# circuito.net
KiCad netlist of a schematic drawn in EAGLE
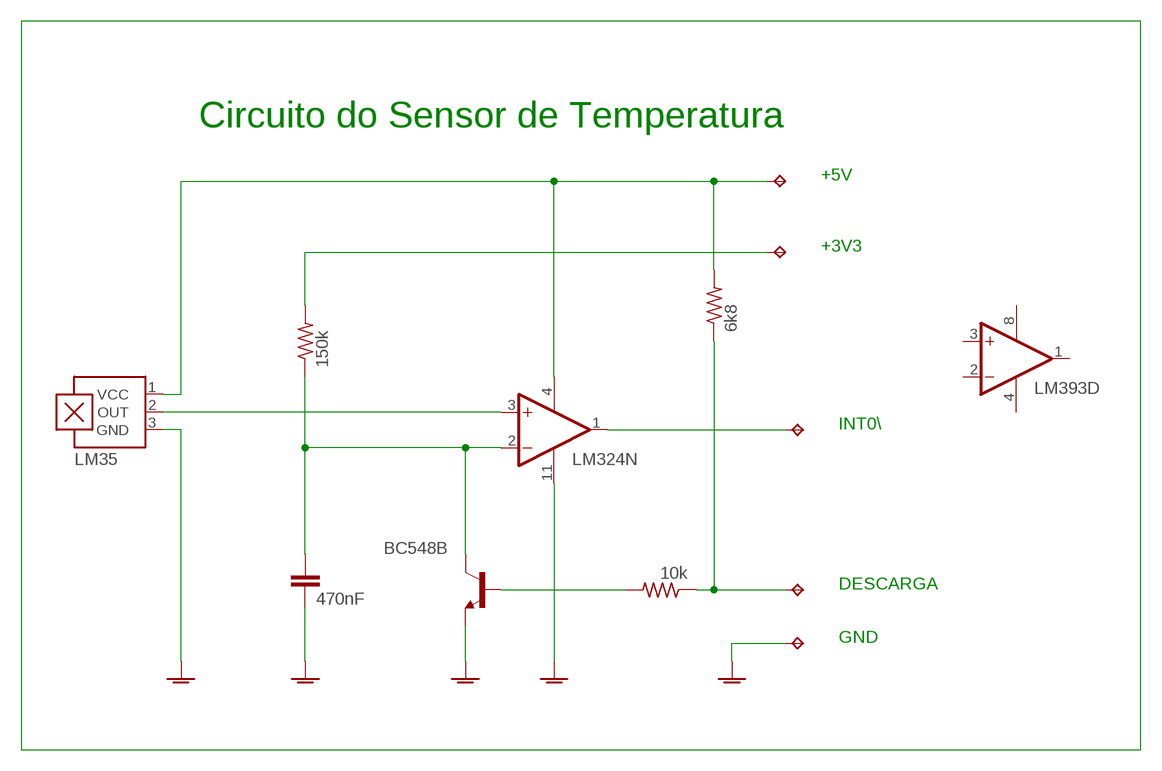
[diagram p0: schematic, sheet 1]

(export (version "E")
  (design (tool "Eeschema 10.0.6"))
  (components
    (comp (ref "C1")
      (value "470nF")
      (footprint "eagle-import:C2.5-3")
      (libsource (lib "eagle-import") (part "C2,5-3"))
    )
    (comp (ref "IC1")
      (value "LM324N")
      (footprint "eagle-import:DIL14")
      (libsource (lib "eagle-import") (part "LM324N"))
    )
    (comp (ref "IC2")
      (value "LM393D")
      (footprint "eagle-import:SO08")
      (libsource (lib "eagle-import") (part "LM393D"))
    )
    (comp (ref "IC3")
      (value "LM35")
      (footprint "eagle-import:SOT23-W")
      (fields (field (name "MF") "ALLEGRO MICROSYSTEMS, INC.") (field (name "MPN") "A1301ELHLT-T"))
      (libsource (lib "eagle-import") (part "A13?LH01"))
    )
    (comp (ref "Q1")
      (value "BC548B")
      (footprint "eagle-import:TO92-EBC")
      (libsource (lib "eagle-import") (part "BC548B"))
    )
    (comp (ref "R1")
      (value "150k")
      (footprint "eagle-import:0207_10")
      (libsource (lib "eagle-import") (part "R-US_0207/10"))
    )
    (comp (ref "R2")
      (value "10k")
      (footprint "eagle-import:0207_10")
      (libsource (lib "eagle-import") (part "R-US_0207/10"))
    )
    (comp (ref "R3")
      (value "6k8")
      (footprint "eagle-import:0207_10")
      (libsource (lib "eagle-import") (part "R-US_0207/10"))
    )
    (comp (ref "TP1")
      (value "TPB1,27")
      (footprint "eagle-import:B1,27")
      (libsource (lib "eagle-import") (part "TPB1,27"))
    )
    (comp (ref "TP2")
      (value "TPB1,27")
      (footprint "eagle-import:B1,27")
      (libsource (lib "eagle-import") (part "TPB1,27"))
    )
    (comp (ref "TP3")
      (value "TPB1,27")
      (footprint "eagle-import:B1,27")
      (libsource (lib "eagle-import") (part "TPB1,27"))
    )
    (comp (ref "TP4")
      (value "TPB1,27")
      (footprint "eagle-import:B1,27")
      (libsource (lib "eagle-import") (part "TPB1,27"))
    )
    (comp (ref "TP5")
      (value "TPB1,27")
      (footprint "eagle-import:B1,27")
      (libsource (lib "eagle-import") (part "TPB1,27"))
    )
  )
  (nets
    (net (code "1") (name "/V+") (class "Default")
      (node (ref "IC2") (pin "8") (pinfunction "V+_8") (pintype "power_in"))
    )
    (net (code "2") (name "/V-") (class "Default")
      (node (ref "IC2") (pin "4") (pinfunction "V-_4") (pintype "power_in"))
    )
    (net (code "3") (name "GNDA") (class "Default")
      (node (ref "C1") (pin "2") (pinfunction "2_2") (pintype "passive"))
      (node (ref "IC1") (pin "11") (pinfunction "V-_11") (pintype "power_in"))
      (node (ref "IC3") (pin "3") (pinfunction "GND_3") (pintype "power_in"))
      (node (ref "Q1") (pin "E") (pinfunction "E_E") (pintype "passive"))
      (node (ref "TP2") (pin "TP") (pinfunction "TP_TP") (pintype "input"))
    )
    (net (code "4") (name "Net-(IC1A-+IN)") (class "Default")
      (node (ref "IC1") (pin "3") (pinfunction "+IN_3") (pintype "input"))
      (node (ref "IC3") (pin "2") (pinfunction "OUT_2") (pintype "output"))
    )
    (net (code "5") (name "Net-(IC1A--IN)") (class "Default")
      (node (ref "C1") (pin "1") (pinfunction "1_1") (pintype "passive"))
      (node (ref "IC1") (pin "2") (pinfunction "-IN_2") (pintype "input"))
      (node (ref "Q1") (pin "C") (pinfunction "C_C") (pintype "passive"))
      (node (ref "R1") (pin "1") (pinfunction "1_1") (pintype "passive"))
    )
    (net (code "6") (name "Net-(IC1A-OUT)") (class "Default")
      (node (ref "IC1") (pin "1") (pinfunction "OUT_1") (pintype "output"))
      (node (ref "TP4") (pin "TP") (pinfunction "TP_TP") (pintype "input"))
    )
    (net (code "7") (name "Net-(IC1E-V+)") (class "Default")
      (node (ref "IC1") (pin "4") (pinfunction "V+_4") (pintype "power_in"))
      (node (ref "IC3") (pin "1") (pinfunction "VCC_1") (pintype "power_in"))
      (node (ref "R3") (pin "2") (pinfunction "2_2") (pintype "passive"))
      (node (ref "TP1") (pin "TP") (pinfunction "TP_TP") (pintype "input"))
    )
    (net (code "8") (name "Net-(Q1-PadB)") (class "Default")
      (node (ref "Q1") (pin "B") (pinfunction "B_B") (pintype "passive"))
      (node (ref "R2") (pin "2") (pinfunction "2_2") (pintype "passive"))
    )
    (net (code "9") (name "Net-(R1-Pad2)") (class "Default")
      (node (ref "R1") (pin "2") (pinfunction "2_2") (pintype "passive"))
      (node (ref "TP5") (pin "TP") (pinfunction "TP_TP") (pintype "input"))
    )
    (net (code "10") (name "Net-(R2-Pad1)") (class "Default")
      (node (ref "R2") (pin "1") (pinfunction "1_1") (pintype "passive"))
      (node (ref "R3") (pin "1") (pinfunction "1_1") (pintype "passive"))
      (node (ref "TP3") (pin "TP") (pinfunction "TP_TP") (pintype "input"))
    )
    (net (code "11") (name "unconnected-(IC2A-+IN-Pad3)") (class "Default")
      (node (ref "IC2") (pin "3") (pinfunction "+IN_3") (pintype "input"))
    )
    (net (code "12") (name "unconnected-(IC2A--IN-Pad2)") (class "Default")
      (node (ref "IC2") (pin "2") (pinfunction "-IN_2") (pintype "input"))
    )
    (net (code "13") (name "unconnected-(IC2A-OUT-Pad1)") (class "Default")
      (node (ref "IC2") (pin "1") (pinfunction "OUT_1") (pintype "output"))
    )
  )
)
